# 2wire.net
KiCad netlist of a schematic drawn in Altium Designer
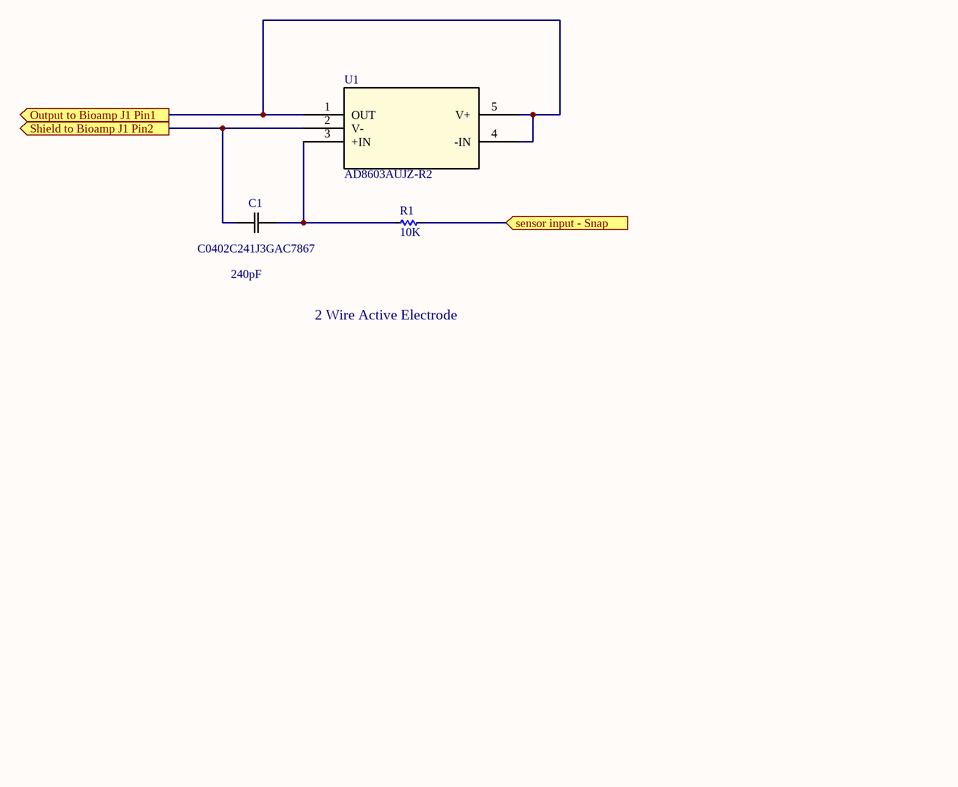
[diagram p0: 2wire.SchDoc]

(export (version "E")
  (design (tool "Eeschema 10.0.6"))
  (components
    (comp (ref "C1")
      (value "C0402C241J3GAC7867")
      (footprint "G-155")
      (description "Imported")
      (libsource (lib "C0402C241J3GAC7867") (part "C0402C241J3GAC7867"))
    )
    (comp (ref "R1")
      (value "10K")
      (footprint "R0402")
      (description "RES, 10K, 0.1%, 1/16W, 0402")
      (fields (field (name "MFG") "PANASONIC") (field (name "POWER") "1/16W"))
      (libsource (lib "AltiumReleaseLibDB") (part "__Template_Resistor"))
    )
    (comp (ref "U1")
      (value "AD8603AUJZ-R2")
      (footprint "UJ_5")
      (description "No Description Available")
      (fields (field (name "COPYRIGHT") "Copyright (C) 2018 Accelerated Designs. All rights reserved"))
      (libsource (lib "AD8603AUJZ") (part "AD8603AUJZ-R2"))
    )
  )
  (nets
    (net (code "1") (name "/Output to Bioamp J1 Pin1") (class "Default")
      (node (ref "U1") (pin "1") (pinfunction "OUT_1") (pintype "passive"))
      (node (ref "U1") (pin "4") (pinfunction "-IN_4") (pintype "passive"))
      (node (ref "U1") (pin "5") (pinfunction "V+_5") (pintype "passive"))
    )
    (net (code "2") (name "/Shield to Bioamp J1 Pin2") (class "Default")
      (node (ref "C1") (pin "1") (pinfunction "1_1") (pintype "passive"))
      (node (ref "U1") (pin "2") (pinfunction "V-_2") (pintype "passive"))
    )
    (net (code "3") (name "/sensor input - Snap") (class "Default")
      (node (ref "R1") (pin "2") (pintype "passive"))
    )
    (net (code "4") (name "Net-(U1-+IN)") (class "Default")
      (node (ref "C1") (pin "2") (pinfunction "2_2") (pintype "passive"))
      (node (ref "R1") (pin "1") (pintype "passive"))
      (node (ref "U1") (pin "3") (pinfunction "+IN_3") (pintype "passive"))
    )
  )
)
